# 10_Misc.net
KiCad netlist of a schematic drawn in Altium Designer
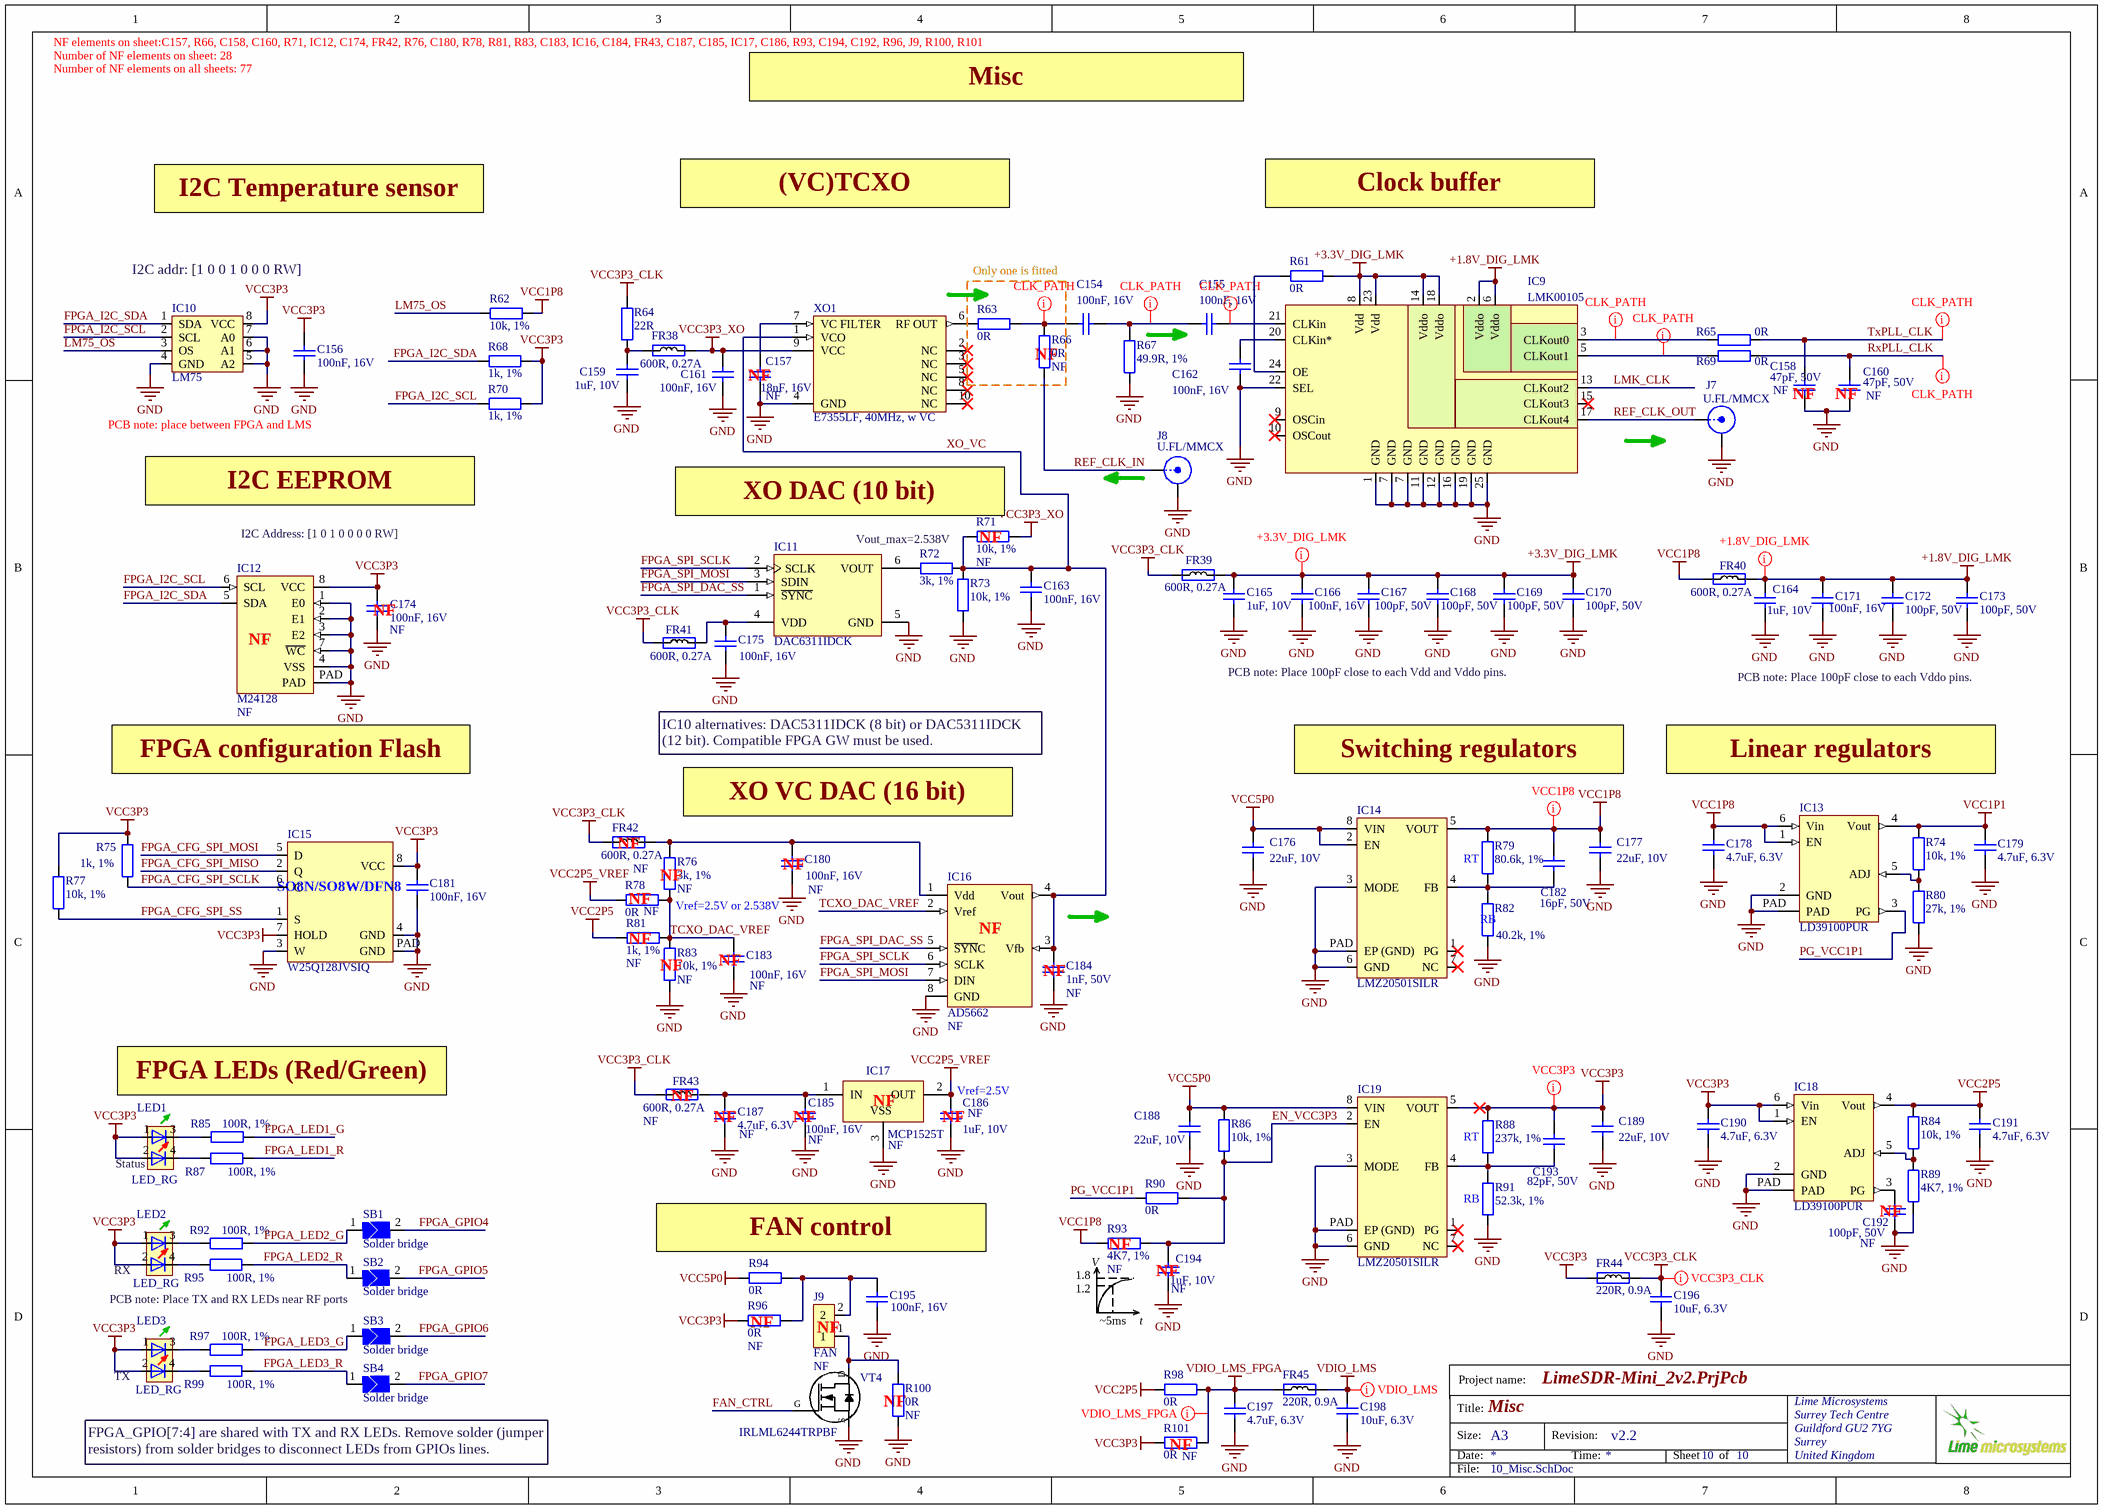
[diagram p0: 10_Misc.SchDoc]

(export (version "E")
  (design (tool "Eeschema 10.0.6"))
  (components
    (comp (ref "C154")
      (value "100nF, 16V")
      (footprint "CAP0402")
      (fields
        (field (name "MANUFACTURER") "Murata Electronics")
        (field (name "TOLERANCE") "10 %")
        (field (name "MANUFACTURER PART NUMBER") "GRM155R71C104KA88D")
      )
      (libsource (lib "LimeMicroAltiumLib_schLib") (part "Cap_0402"))
    )
    (comp (ref "C155")
      (value "100nF, 16V")
      (footprint "CAP0402")
      (fields
        (field (name "MANUFACTURER") "Murata Electronics")
        (field (name "TOLERANCE") "10 %")
        (field (name "MANUFACTURER PART NUMBER") "GRM155R71C104KA88D")
      )
      (libsource (lib "LimeMicroAltiumLib_schLib") (part "Cap_0402"))
    )
    (comp (ref "C156")
      (value "100nF, 16V")
      (footprint "CAP0402")
      (fields
        (field (name "TOLERANCE") "10 %")
        (field (name "MANUFACTURER") "Murata Electronics")
        (field (name "MANUFACTURER PART NUMBER") "GRM155R71C104KA88D")
      )
      (libsource (lib "LimeFPGAboard_schLib") (part "Cap_0603"))
    )
    (comp (ref "C157")
      (value "18nF, 16V")
      (footprint "CAP0402")
      (fields
        (field (name "ASSEMBLY INFO") "NF")
        (field (name "MANUFACTURER") "Yageo")
        (field (name "TOLERANCE") "±10%")
      )
      (libsource (lib "LimeMicroAltiumLib_schLib") (part "Cap_0402"))
    )
    (comp (ref "C158")
      (value "47pF, 50V")
      (footprint "CAP0402")
      (fields
        (field (name "TOLERANCE") "±1%")
        (field (name "MANUFACTURER") "TDK Corporation")
        (field (name "ASSEMBLY INFO") "NF")
      )
      (libsource (lib "LimeMicroAltiumLib_schLib") (part "Cap_0402"))
    )
    (comp (ref "C159")
      (value "1uF, 10V")
      (footprint "CAP0402")
      (fields (field (name "MANUFACTURER") "TDK"))
      (libsource (lib "LimeMicroAltiumLib_schLib") (part "Cap_0402"))
    )
    (comp (ref "C160")
      (value "47pF, 50V")
      (footprint "CAP0402")
      (fields
        (field (name "TOLERANCE") "±1%")
        (field (name "MANUFACTURER") "TDK Corporation")
        (field (name "ASSEMBLY INFO") "NF")
      )
      (libsource (lib "LimeMicroAltiumLib_schLib") (part "Cap_0402"))
    )
    (comp (ref "C161")
      (value "100nF, 16V")
      (footprint "CAP0402")
      (fields
        (field (name "MANUFACTURER") "Murata Electronics")
        (field (name "TOLERANCE") "10 %")
        (field (name "MANUFACTURER PART NUMBER") "GRM155R71C104KA88D")
      )
      (libsource (lib "LimeMicroAltiumLib_schLib") (part "Cap_0402"))
    )
    (comp (ref "C162")
      (value "100nF, 16V")
      (footprint "CAP0402")
      (fields
        (field (name "MANUFACTURER") "Murata Electronics")
        (field (name "TOLERANCE") "10 %")
        (field (name "MANUFACTURER PART NUMBER") "GRM155R71C104KA88D")
      )
      (libsource (lib "LimeMicroAltiumLib_schLib") (part "Cap_0402"))
    )
    (comp (ref "C163")
      (value "100nF, 16V")
      (footprint "CAP0402")
      (fields
        (field (name "MANUFACTURER") "Murata Electronics")
        (field (name "TOLERANCE") "10 %")
        (field (name "MANUFACTURER PART NUMBER") "GRM155R71C104KA88D")
      )
      (libsource (lib "LimeMicroAltiumLib_schLib") (part "Cap_0402"))
    )
    (comp (ref "C164")
      (value "1uF, 10V")
      (footprint "CAP0402")
      (fields (field (name "MANUFACTURER") "TDK"))
      (libsource (lib "LimeMicroAltiumLib_schLib") (part "Cap_0402"))
    )
    (comp (ref "C165")
      (value "1uF, 10V")
      (footprint "CAP0402")
      (fields (field (name "MANUFACTURER") "TDK"))
      (libsource (lib "LimeMicroAltiumLib_schLib") (part "Cap_0402"))
    )
    (comp (ref "C166")
      (value "100nF, 16V")
      (footprint "CAP0402")
      (fields
        (field (name "MANUFACTURER") "Murata Electronics")
        (field (name "TOLERANCE") "10 %")
        (field (name "MANUFACTURER PART NUMBER") "GRM155R71C104KA88D")
      )
      (libsource (lib "LimeMicroAltiumLib_schLib") (part "Cap_0402"))
    )
    (comp (ref "C167")
      (value "100pF, 50V")
      (footprint "CAP0402")
      (fields (field (name "MANUFACTURER") "Yageo") (field (name "TOLERANCE") "±5%"))
      (libsource (lib "LimeMicroAltiumLib_schLib") (part "Cap_0402"))
    )
    (comp (ref "C168")
      (value "100pF, 50V")
      (footprint "CAP0402")
      (fields (field (name "MANUFACTURER") "Yageo") (field (name "TOLERANCE") "±5%"))
      (libsource (lib "LimeMicroAltiumLib_schLib") (part "Cap_0402"))
    )
    (comp (ref "C169")
      (value "100pF, 50V")
      (footprint "CAP0402")
      (fields (field (name "MANUFACTURER") "Yageo") (field (name "TOLERANCE") "±5%"))
      (libsource (lib "LimeMicroAltiumLib_schLib") (part "Cap_0402"))
    )
    (comp (ref "C170")
      (value "100pF, 50V")
      (footprint "CAP0402")
      (fields (field (name "MANUFACTURER") "Yageo") (field (name "TOLERANCE") "±5%"))
      (libsource (lib "LimeMicroAltiumLib_schLib") (part "Cap_0402"))
    )
    (comp (ref "C171")
      (value "100nF, 16V")
      (footprint "CAP0402")
      (fields
        (field (name "MANUFACTURER") "Murata Electronics")
        (field (name "TOLERANCE") "10 %")
        (field (name "MANUFACTURER PART NUMBER") "GRM155R71C104KA88D")
      )
      (libsource (lib "LimeMicroAltiumLib_schLib") (part "Cap_0402"))
    )
    (comp (ref "C172")
      (value "100pF, 50V")
      (footprint "CAP0402")
      (fields (field (name "MANUFACTURER") "Yageo") (field (name "TOLERANCE") "±5%"))
      (libsource (lib "LimeMicroAltiumLib_schLib") (part "Cap_0402"))
    )
    (comp (ref "C173")
      (value "100pF, 50V")
      (footprint "CAP0402")
      (fields (field (name "MANUFACTURER") "Yageo") (field (name "TOLERANCE") "±5%"))
      (libsource (lib "LimeMicroAltiumLib_schLib") (part "Cap_0402"))
    )
    (comp (ref "C174")
      (value "100nF, 16V")
      (footprint "CAP0402")
      (fields
        (field (name "TOLERANCE") "10 %")
        (field (name "MANUFACTURER") "Murata Electronics")
        (field (name "MANUFACTURER PART NUMBER") "GRM155R71C104KA88D")
        (field (name "ASSEMBLY INFO") "NF")
      )
      (libsource (lib "LimeFPGAboard_schLib") (part "Cap_0603"))
    )
    (comp (ref "C175")
      (value "100nF, 16V")
      (footprint "CAP0402")
      (fields
        (field (name "TOLERANCE") "10 %")
        (field (name "MANUFACTURER") "Murata Electronics")
        (field (name "MANUFACTURER PART NUMBER") "GRM155R71C104KA88D")
      )
      (libsource (lib "LimeFPGAboard_schLib") (part "Cap_0603"))
    )
    (comp (ref "C176")
      (value "22uF, 10V")
      (footprint "CAP0603")
      (fields (field (name "TOLERANCE") "20 %") (field (name "MANUFACTURER") "TDK Corporation"))
      (libsource (lib "LimeFPGAboard_schLib") (part "Cap_0603"))
    )
    (comp (ref "C177")
      (value "22uF, 10V")
      (footprint "CAP0603")
      (fields (field (name "TOLERANCE") "20 %") (field (name "MANUFACTURER") "TDK Corporation"))
      (libsource (lib "LimeFPGAboard_schLib") (part "Cap_0603"))
    )
    (comp (ref "C178")
      (value "4.7uF, 6.3V")
      (footprint "CAP0402")
      (fields
        (field (name "MANUFACTURER") "Murata Electronics North America")
        (field (name "TOLERANCE") "±20%")
      )
      (libsource (lib "LimeMicroAltiumLib_schLib") (part "Cap_0402"))
    )
    (comp (ref "C179")
      (value "4.7uF, 6.3V")
      (footprint "CAP0402")
      (fields
        (field (name "MANUFACTURER") "Murata Electronics North America")
        (field (name "TOLERANCE") "±20%")
      )
      (libsource (lib "LimeMicroAltiumLib_schLib") (part "Cap_0402"))
    )
    (comp (ref "C180")
      (value "100nF, 16V")
      (footprint "CAP0402")
      (fields
        (field (name "TOLERANCE") "10 %")
        (field (name "MANUFACTURER") "Murata Electronics")
        (field (name "MANUFACTURER PART NUMBER") "GRM155R71C104KA88D")
        (field (name "ASSEMBLY INFO") "NF")
      )
      (libsource (lib "LimeFPGAboard_schLib") (part "Cap_0603"))
    )
    (comp (ref "C181")
      (value "100nF, 16V")
      (footprint "CAP0402")
      (fields
        (field (name "TOLERANCE") "10 %")
        (field (name "MANUFACTURER") "Murata Electronics")
        (field (name "MANUFACTURER PART NUMBER") "GRM155R71C104KA88D")
      )
      (libsource (lib "LimeFPGAboard_schLib") (part "Cap_0603"))
    )
    (comp (ref "C182")
      (value "16pF, 50V")
      (footprint "CAP0402")
      (fields (field (name "MANUFACTURER") "Yageo") (field (name "TOLERANCE") "5%"))
      (libsource (lib "LimeMicroAltiumLib_schLib") (part "Cap_0402"))
    )
    (comp (ref "C183")
      (value "100nF, 16V")
      (footprint "CAP0402")
      (fields
        (field (name "TOLERANCE") "10 %")
        (field (name "MANUFACTURER") "Murata Electronics")
        (field (name "ASSEMBLY INFO") "NF")
      )
      (libsource (lib "") (part "Cap_0603_1"))
    )
    (comp (ref "C184")
      (value "1nF, 50V")
      (footprint "CAP0402")
      (fields
        (field (name "ASSEMBLY INFO") "NF")
        (field (name "TOLERANCE") "10 %")
        (field (name "MANUFACTURER") "Murata Electronics")
      )
      (libsource (lib "") (part "Cap_0402_1"))
    )
    (comp (ref "C185")
      (value "100nF, 16V")
      (footprint "CAP0402")
      (fields
        (field (name "TOLERANCE") "10 %")
        (field (name "MANUFACTURER") "Murata Electronics")
        (field (name "ASSEMBLY INFO") "NF")
      )
      (libsource (lib "") (part "Cap_0603_1"))
    )
    (comp (ref "C186")
      (value "1uF, 10V")
      (footprint "CAP0402")
      (fields (field (name "ASSEMBLY INFO") "NF") (field (name "MANUFACTURER") "TDK"))
      (libsource (lib "LimeMicroAltiumLib_schLib") (part "Cap_0402"))
    )
    (comp (ref "C187")
      (value "4.7uF, 6.3V")
      (footprint "CAP0402")
      (fields
        (field (name "ASSEMBLY INFO") "NF")
        (field (name "MANUFACTURER") "Murata Electronics North America")
        (field (name "TOLERANCE") "±20%")
      )
      (libsource (lib "LimeMicroAltiumLib_schLib") (part "Cap_0402"))
    )
    (comp (ref "C188")
      (value "22uF, 10V")
      (footprint "CAP0603")
      (fields (field (name "TOLERANCE") "20 %") (field (name "MANUFACTURER") "TDK Corporation"))
      (libsource (lib "LimeFPGAboard_schLib") (part "Cap_0603"))
    )
    (comp (ref "C189")
      (value "22uF, 10V")
      (footprint "CAP0603")
      (fields (field (name "TOLERANCE") "20 %") (field (name "MANUFACTURER") "TDK Corporation"))
      (libsource (lib "LimeFPGAboard_schLib") (part "Cap_0603"))
    )
    (comp (ref "C190")
      (value "4.7uF, 6.3V")
      (footprint "CAP0402")
      (fields
        (field (name "MANUFACTURER") "Murata Electronics North America")
        (field (name "TOLERANCE") "±20%")
      )
      (libsource (lib "LimeMicroAltiumLib_schLib") (part "Cap_0402"))
    )
    (comp (ref "C191")
      (value "4.7uF, 6.3V")
      (footprint "CAP0402")
      (fields
        (field (name "MANUFACTURER") "Murata Electronics North America")
        (field (name "TOLERANCE") "±20%")
      )
      (libsource (lib "LimeMicroAltiumLib_schLib") (part "Cap_0402"))
    )
    (comp (ref "C192")
      (value "100pF, 50V")
      (footprint "CAP0402")
      (fields
        (field (name "ASSEMBLY INFO") "NF")
        (field (name "MANUFACTURER") "Yageo")
        (field (name "TOLERANCE") "±5%")
      )
      (libsource (lib "LimeMicroAltiumLib_schLib") (part "Cap_0402"))
    )
    (comp (ref "C193")
      (value "82pF, 50V")
      (footprint "CAP0402")
      (description "Cap Cer 82PF 50V Ch 0402")
      (fields (field (name "MANUFACTURER") "Taiyo Yuden"))
      (libsource (lib "LimeMicroAltiumLib_schLib") (part "Cap_0402"))
    )
    (comp (ref "C194")
      (value "1uF, 10V")
      (footprint "CAP0402")
      (fields (field (name "ASSEMBLY INFO") "NF") (field (name "MANUFACTURER") "TDK"))
      (libsource (lib "LimeMicroAltiumLib_schLib") (part "Cap_0402"))
    )
    (comp (ref "C195")
      (value "100nF, 16V")
      (footprint "CAP0402")
      (fields
        (field (name "TOLERANCE") "10 %")
        (field (name "MANUFACTURER") "Murata Electronics")
        (field (name "MANUFACTURER PART NUMBER") "GRM155R71C104KA88D")
      )
      (libsource (lib "LimeFPGAboard_schLib") (part "Cap_0603"))
    )
    (comp (ref "C196")
      (value "10uF, 6.3V")
      (footprint "CAP0603")
      (fields (field (name "TOLERANCE") "±20%") (field (name "MANUFACTURER") "Yageo"))
      (libsource (lib "LimeFPGAboard_schLib") (part "Cap_0603"))
    )
    (comp (ref "C197")
      (value "4.7uF, 6.3V")
      (footprint "CAP0402")
      (fields
        (field (name "MANUFACTURER") "Murata Electronics North America")
        (field (name "TOLERANCE") "±20%")
      )
      (libsource (lib "LimeMicroAltiumLib_schLib") (part "Cap_0402"))
    )
    (comp (ref "C198")
      (value "10uF, 6.3V")
      (footprint "CAP0603")
      (fields (field (name "TOLERANCE") "±20%") (field (name "MANUFACTURER") "Yageo"))
      (libsource (lib "LimeFPGAboard_schLib") (part "Cap_0603"))
    )
    (comp (ref "FR38")
      (value "600R, 0.27A")
      (footprint "RES0201")
      (fields (field (name "MANUFACTURER") "Taiyo Yuden"))
      (libsource (lib "LimeMicroAltiumLib_schLib") (part "Ferrite"))
    )
    (comp (ref "FR39")
      (value "600R, 0.27A")
      (footprint "RES0201")
      (fields (field (name "MANUFACTURER") "Taiyo Yuden"))
      (libsource (lib "LimeMicroAltiumLib_schLib") (part "Ferrite"))
    )
    (comp (ref "FR40")
      (value "600R, 0.27A")
      (footprint "RES0201")
      (fields (field (name "MANUFACTURER") "Taiyo Yuden"))
      (libsource (lib "LimeMicroAltiumLib_schLib") (part "Ferrite"))
    )
    (comp (ref "FR41")
      (value "600R, 0.27A")
      (footprint "RES0201")
      (fields (field (name "MANUFACTURER") "Taiyo Yuden"))
      (libsource (lib "LimeMicroAltiumLib_schLib") (part "Ferrite"))
    )
    (comp (ref "FR42")
      (value "600R, 0.27A")
      (footprint "RES0201")
      (fields (field (name "MANUFACTURER") "Taiyo Yuden") (field (name "ASSEMBLY INFO") "NF"))
      (libsource (lib "LimeMicroAltiumLib_schLib") (part "Ferrite"))
    )
    (comp (ref "FR43")
      (value "600R, 0.27A")
      (footprint "RES0201")
      (fields (field (name "MANUFACTURER") "Taiyo Yuden") (field (name "ASSEMBLY INFO") "NF"))
      (libsource (lib "LimeMicroAltiumLib_schLib") (part "Ferrite"))
    )
    (comp (ref "FR44")
      (value "220R, 0.9A")
      (footprint "RES0402")
      (fields (field (name "MANUFACTURER") "TDK Corporation"))
      (libsource (lib "LimeFPGAboard_schLib") (part "Ferrite"))
    )
    (comp (ref "FR45")
      (value "220R, 0.9A")
      (footprint "RES0402")
      (fields (field (name "MANUFACTURER") "TDK Corporation"))
      (libsource (lib "LimeFPGAboard_schLib") (part "Ferrite"))
    )
    (comp (ref "IC9")
      (value "LMK00105")
      (footprint "LMK00105SQ")
      (fields (field (name "MANUFACTURER") "Texas Instruments"))
      (libsource (lib "LimeMicroAltiumLib_schLib") (part "LMK00105"))
    )
    (comp (ref "IC10")
      (value "LM75")
      (footprint "HWSON8_LM75")
      (fields (field (name "MANUFACTURER") "NXP Semiconductors"))
      (libsource (lib "LimeMicroAltiumLib_schLib") (part "LM75"))
    )
    (comp (ref "IC11")
      (value "DAC6311IDCK")
      (footprint "AD5601_SOT23-6")
      (fields (field (name "MANUFACTURER") "Texas Instruments"))
      (libsource (lib "LimeMicroAltiumLib_schLib") (part "AD5601BKSZ-REEL7"))
    )
    (comp (ref "IC12")
      (value "M24128")
      (footprint "M24128-DFMC6TG")
      (fields (field (name "MANUFACTURER") "STMicroelectronics") (field (name "ASSEMBLY INFO") "NF"))
      (libsource (lib "LimeMicroAltiumLib_schLib") (part "M24128-DFMC6TG"))
    )
    (comp (ref "IC13")
      (value "LD39100PUR")
      (footprint "LD39100PUR")
      (fields (field (name "MANUFACTURER") "STMicroelectronics"))
      (libsource (lib "LimeMicroAltiumLib_schLib") (part "LD39100PUR"))
    )
    (comp (ref "IC14")
      (value "LMZ20501SILR")
      (footprint "LMZ20501SILR_DC-DC_8-SMD")
      (fields (field (name "MANUFACTURER") "Texas Instruments"))
      (libsource (lib "LimeMicroAltiumLib_schLib_r04") (part "LMZ20501SILR_DC-DC"))
    )
    (comp (ref "IC15")
      (value "W25Q128JVSIQ")
      (footprint "S25FL164K_WSON8_DFN6")
      (fields (field (name "MANUFACTURER") "Winbond"))
      (libsource (lib "LimeMicroAltiumLib_schLib_r03") (part "M25P40_with_pad"))
    )
    (comp (ref "IC16")
      (value "AD5662")
      (footprint "AD5662_SOT23-8")
      (fields (field (name "MANUFACTURER") "Analog Devices Inc.") (field (name "ASSEMBLY INFO") "NF"))
      (libsource (lib "LimeMicroAltiumLib_schLib") (part "AD5662"))
    )
    (comp (ref "IC17")
      (value "MCP1525T")
      (footprint "SOT23-3_v2")
      (description "2.5V Voltage Reference, 3-Pin SOT-23, Industrial Temperature, Tape and Reel")
      (fields
        (field (name "MANUFACTURER") "Microchip Technology")
        (field (name "TOLERANCE") "±1%")
        (field (name "ASSEMBLY INFO") "NF")
      )
      (libsource (lib "LimeMicroAltiumLib_schLib") (part "MCP1525T-I/TT"))
    )
    (comp (ref "IC18")
      (value "LD39100PUR")
      (footprint "LD39100PUR")
      (fields (field (name "MANUFACTURER") "STMicroelectronics"))
      (libsource (lib "LimeMicroAltiumLib_schLib") (part "LD39100PUR"))
    )
    (comp (ref "IC19")
      (value "LMZ20501SILR")
      (footprint "LMZ20501SILR_DC-DC_8-SMD")
      (fields (field (name "MANUFACTURER") "Texas Instruments"))
      (libsource (lib "LimeMicroAltiumLib_schLib_r04") (part "LMZ20501SILR_DC-DC"))
    )
    (comp (ref "J7")
      (value "U.FL/MMCX")
      (footprint "MMCX_UFL_conn_u")
      (description "CONN UMC RCPT STR 50 OHM SMD")
      (fields (field (name "MANUFACTURER") "Molex, LLC"))
      (libsource (lib "LimeMicroAltiumLib_schLib") (part "RF_IF_connector"))
    )
    (comp (ref "J8")
      (value "U.FL/MMCX")
      (footprint "MMCX_UFL_conn_u")
      (description "CONN UMC RCPT STR 50 OHM SMD")
      (fields (field (name "MANUFACTURER") "Molex, LLC"))
      (libsource (lib "LimeMicroAltiumLib_schLib") (part "RF_IF_connector"))
    )
    (comp (ref "J9")
      (value "FAN")
      (footprint "Header2x1_TH_v2")
      (fields (field (name "ASSEMBLY INFO") "NF") (field (name "MANUFACTURER") "3M"))
      (libsource (lib "LimeFPGAboard_schLib") (part "Jumper"))
    )
    (comp (ref "LED1")
      (value "LED_RG")
      (footprint "LED-2x0603")
      (fields (field (name "MANUFACTURER") "Avago Technologies US Inc."))
      (libsource (lib "LimeMicroAltiumLib_schLib") (part "LED_green_red_SMD"))
    )
    (comp (ref "LED2")
      (value "LED_RG")
      (footprint "LED-2x0603")
      (fields (field (name "MANUFACTURER") "Avago Technologies US Inc."))
      (libsource (lib "LimeMicroAltiumLib_schLib") (part "LED_green_red_SMD"))
    )
    (comp (ref "LED3")
      (value "LED_RG")
      (footprint "LED-2x0603")
      (fields (field (name "MANUFACTURER") "Avago Technologies US Inc."))
      (libsource (lib "LimeMicroAltiumLib_schLib") (part "LED_green_red_SMD"))
    )
    (comp (ref "R61")
      (value "0R")
      (footprint "RES0402")
      (fields (field (name "MANUFACTURER") "Yageo") (field (name "TOLERANCE") "Jumper"))
      (libsource (lib "LimeMicroAltiumLib_schLib") (part "Res_0402"))
    )
    (comp (ref "R62")
      (value "10k, 1%")
      (footprint "RES0402")
      (fields (field (name "MANUFACTURER") "Yageo") (field (name "TOLERANCE") "±1%"))
      (libsource (lib "LimeMicroAltiumLib_schLib") (part "Res_0402"))
    )
    (comp (ref "R63")
      (value "0R")
      (footprint "RES0402")
      (fields (field (name "MANUFACTURER") "Yageo") (field (name "TOLERANCE") "Jumper"))
      (libsource (lib "LimeMicroAltiumLib_schLib") (part "Res_0402"))
    )
    (comp (ref "R64")
      (value "22R")
      (footprint "RES0402")
      (fields (field (name "TOLERANCE") "±1%") (field (name "MANUFACTURER") "Yageo"))
      (libsource (lib "LimeFPGAboard_schLib") (part "Res_0402"))
    )
    (comp (ref "R65")
      (value "0R")
      (footprint "RES0402")
      (fields (field (name "MANUFACTURER") "Yageo") (field (name "TOLERANCE") "Jumper"))
      (libsource (lib "LimeFPGAboard_schLib") (part "Res_0402"))
    )
    (comp (ref "R66")
      (value "0R")
      (footprint "RES0402")
      (fields
        (field (name "ASSEMBLY INFO") "NF")
        (field (name "MANUFACTURER") "Yageo")
        (field (name "TOLERANCE") "Jumper")
      )
      (libsource (lib "LimeMicroAltiumLib_schLib") (part "Res_0402"))
    )
    (comp (ref "R67")
      (value "49.9R, 1%")
      (footprint "RES0402")
      (fields
        (field (name "TOLERANCE") "±1%")
        (field (name "MANUFACTURER") "Samsung Electro-Mechanics America, Inc.")
      )
      (libsource (lib "LimeMicroAltiumLib_schLib") (part "Res_0402"))
    )
    (comp (ref "R68")
      (value "1k, 1%")
      (footprint "RES0402")
      (fields (field (name "MANUFACTURER") "Stackpole Electronics Inc") (field (name "TOLERANCE") "±1%"))
      (libsource (lib "LimeMicroAltiumLib_schLib") (part "Res_0402"))
    )
    (comp (ref "R69")
      (value "0R")
      (footprint "RES0402")
      (fields (field (name "MANUFACTURER") "Yageo") (field (name "TOLERANCE") "Jumper"))
      (libsource (lib "LimeFPGAboard_schLib") (part "Res_0402"))
    )
    (comp (ref "R70")
      (value "1k, 1%")
      (footprint "RES0402")
      (fields (field (name "MANUFACTURER") "Stackpole Electronics Inc") (field (name "TOLERANCE") "±1%"))
      (libsource (lib "LimeMicroAltiumLib_schLib") (part "Res_0402"))
    )
    (comp (ref "R71")
      (value "10k, 1%")
      (footprint "RES0402")
      (fields
        (field (name "ASSEMBLY INFO") "NF")
        (field (name "MANUFACTURER") "Yageo")
        (field (name "TOLERANCE") "±1%")
      )
      (libsource (lib "LimeMicroAltiumLib_schLib") (part "Res_0402"))
    )
    (comp (ref "R72")
      (value "3k, 1%")
      (footprint "RES0402")
      (fields (field (name "TOLERANCE") "±1%") (field (name "MANUFACTURER") "Vishay Dale"))
      (libsource (lib "LimeMicroAltiumLib_schLib") (part "Res_0402"))
    )
    (comp (ref "R73")
      (value "10k, 1%")
      (footprint "RES0402")
      (fields (field (name "MANUFACTURER") "Yageo") (field (name "TOLERANCE") "±1%"))
      (libsource (lib "LimeMicroAltiumLib_schLib") (part "Res_0402"))
    )
    (comp (ref "R74")
      (value "10k, 1%")
      (footprint "RES0402")
      (fields (field (name "MANUFACTURER") "Yageo") (field (name "TOLERANCE") "±1%"))
      (libsource (lib "LimeMicroAltiumLib_schLib") (part "Res_0402"))
    )
    (comp (ref "R75")
      (value "1k, 1%")
      (footprint "RES0402")
      (fields (field (name "MANUFACTURER") "Stackpole Electronics Inc") (field (name "TOLERANCE") "±1%"))
      (libsource (lib "LimeMicroAltiumLib_schLib") (part "Res_0402"))
    )
    (comp (ref "R76")
      (value "3k, 1%")
      (footprint "RES0402")
      (fields
        (field (name "ASSEMBLY INFO") "NF")
        (field (name "TOLERANCE") "±1%")
        (field (name "MANUFACTURER") "Vishay Dale")
      )
      (libsource (lib "") (part "Res_0402_1"))
    )
    (comp (ref "R77")
      (value "10k, 1%")
      (footprint "RES0402")
      (fields (field (name "MANUFACTURER") "Yageo") (field (name "TOLERANCE") "±1%"))
      (libsource (lib "LimeMicroAltiumLib_schLib") (part "Res_0402"))
    )
    (comp (ref "R78")
      (value "0R")
      (footprint "RES0402")
      (fields
        (field (name "ASSEMBLY INFO") "NF")
        (field (name "MANUFACTURER") "Yageo")
        (field (name "TOLERANCE") "Jumper")
      )
      (libsource (lib "LimeMicroAltiumLib_schLib") (part "Res_0402"))
    )
    (comp (ref "R79")
      (value "80.6k, 1%")
      (footprint "RES0402")
      (fields (field (name "MANUFACTURER") "Stackpole Electronics") (field (name "TOLERANCE") "1%"))
      (libsource (lib "LimeMicroAltiumLib_schLib") (part "Res_0402"))
    )
    (comp (ref "R80")
      (value "27k, 1%")
      (footprint "RES0402")
      (fields (field (name "MANUFACTURER") "Yageo") (field (name "TOLERANCE") "1%"))
      (libsource (lib "LimeFPGAboard_schLib") (part "Res_0402"))
    )
    (comp (ref "R81")
      (value "1k, 1%")
      (footprint "RES0402")
      (fields
        (field (name "ASSEMBLY INFO") "NF")
        (field (name "MANUFACTURER") "Stackpole Electronics Inc")
        (field (name "TOLERANCE") "±1%")
      )
      (libsource (lib "") (part "Res_0402_1"))
    )
    (comp (ref "R82")
      (value "40.2k, 1%")
      (footprint "RES0402")
      (fields (field (name "MANUFACTURER") "Yageo") (field (name "TOLERANCE") "1%"))
      (libsource (lib "LimeMicroAltiumLib_schLib") (part "Res_0402"))
    )
    (comp (ref "R83")
      (value "10k, 1%")
      (footprint "RES0402")
      (fields
        (field (name "ASSEMBLY INFO") "NF")
        (field (name "MANUFACTURER") "Yageo")
        (field (name "TOLERANCE") "±1%")
      )
      (libsource (lib "") (part "Res_0402_1"))
    )
    (comp (ref "R84")
      (value "10k, 1%")
      (footprint "RES0402")
      (fields (field (name "MANUFACTURER") "Yageo") (field (name "TOLERANCE") "±1%"))
      (libsource (lib "LimeMicroAltiumLib_schLib") (part "Res_0402"))
    )
    (comp (ref "R85")
      (value "100R, 1%")
      (footprint "RES0402")
      (fields (field (name "TOLERANCE") "±1%") (field (name "MANUFACTURER") "Stackpole Electronics Inc."))
      (libsource (lib "LimeMicroAltiumLib_schLib") (part "Res_0402"))
    )
    (comp (ref "R86")
      (value "10k, 1%")
      (footprint "RES0402")
      (fields (field (name "MANUFACTURER") "Yageo") (field (name "TOLERANCE") "±1%"))
      (libsource (lib "LimeMicroAltiumLib_schLib") (part "Res_0402"))
    )
    (comp (ref "R87")
      (value "100R, 1%")
      (footprint "RES0402")
      (fields (field (name "TOLERANCE") "±1%") (field (name "MANUFACTURER") "Stackpole Electronics Inc."))
      (libsource (lib "LimeMicroAltiumLib_schLib") (part "Res_0402"))
    )
    (comp (ref "R88")
      (value "237k, 1%")
      (footprint "RES0402")
      (fields (field (name "MANUFACTURER") "Yageo") (field (name "TOLERANCE") "1%"))
      (libsource (lib "LimeMicroAltiumLib_schLib") (part "Res_0402"))
    )
    (comp (ref "R89")
      (value "4K7, 1%")
      (footprint "RES0402")
      (fields (field (name "MANUFACTURER") "Yageo") (field (name "TOLERANCE") "±1%"))
      (libsource (lib "LimeFPGAboard_schLib") (part "Res_0402"))
    )
    (comp (ref "R90")
      (value "0R")
      (footprint "RES0402")
      (fields (field (name "MANUFACTURER") "Yageo") (field (name "TOLERANCE") "Jumper"))
      (libsource (lib "LimeMicroAltiumLib_schLib") (part "Res_0402"))
    )
    (comp (ref "R91")
      (value "52.3k, 1%")
      (footprint "RES0402")
      (fields (field (name "MANUFACTURER") "Panasonic") (field (name "TOLERANCE") "1%"))
      (libsource (lib "LimeMicroAltiumLib_schLib") (part "Res_0402"))
    )
    (comp (ref "R92")
      (value "100R, 1%")
      (footprint "RES0402")
      (fields (field (name "TOLERANCE") "±1%") (field (name "MANUFACTURER") "Stackpole Electronics Inc."))
      (libsource (lib "LimeMicroAltiumLib_schLib") (part "Res_0402"))
    )
    (comp (ref "R93")
      (value "4K7, 1%")
      (footprint "RES0402")
      (fields
        (field (name "MANUFACTURER") "Yageo")
        (field (name "TOLERANCE") "±1%")
        (field (name "ASSEMBLY INFO") "NF")
      )
      (libsource (lib "LimeFPGAboard_schLib") (part "Res_0402"))
    )
    (comp (ref "R94")
      (value "0R")
      (footprint "RES0402")
      (fields (field (name "MANUFACTURER") "Yageo") (field (name "TOLERANCE") "Jumper"))
      (libsource (lib "LimeMicroAltiumLib_schLib") (part "Res_0402"))
    )
    (comp (ref "R95")
      (value "100R, 1%")
      (footprint "RES0402")
      (fields (field (name "TOLERANCE") "±1%") (field (name "MANUFACTURER") "Stackpole Electronics Inc."))
      (libsource (lib "LimeMicroAltiumLib_schLib") (part "Res_0402"))
    )
    (comp (ref "R96")
      (value "0R")
      (footprint "RES0402")
      (fields
        (field (name "ASSEMBLY INFO") "NF")
        (field (name "MANUFACTURER") "Yageo")
        (field (name "TOLERANCE") "Jumper")
      )
      (libsource (lib "LimeMicroAltiumLib_schLib") (part "Res_0402"))
    )
    (comp (ref "R97")
      (value "100R, 1%")
      (footprint "RES0402")
      (fields (field (name "TOLERANCE") "±1%") (field (name "MANUFACTURER") "Stackpole Electronics Inc."))
      (libsource (lib "LimeMicroAltiumLib_schLib") (part "Res_0402"))
    )
    (comp (ref "R98")
      (value "0R")
      (footprint "RES0402")
      (fields (field (name "MANUFACTURER") "Yageo") (field (name "TOLERANCE") "Jumper"))
      (libsource (lib "LimeFPGAboard_schLib") (part "Res_0402"))
    )
    (comp (ref "R99")
      (value "100R, 1%")
      (footprint "RES0402")
      (fields (field (name "TOLERANCE") "±1%") (field (name "MANUFACTURER") "Stackpole Electronics Inc."))
      (libsource (lib "LimeMicroAltiumLib_schLib") (part "Res_0402"))
    )
    (comp (ref "R100")
      (value "0R")
      (footprint "RES0402")
      (fields
        (field (name "ASSEMBLY INFO") "NF")
        (field (name "MANUFACTURER") "Yageo")
        (field (name "TOLERANCE") "Jumper")
      )
      (libsource (lib "LimeMicroAltiumLib_schLib") (part "Res_0402"))
    )
    (comp (ref "R101")
      (value "0R")
      (footprint "RES0402")
      (fields
        (field (name "MANUFACTURER") "Yageo")
        (field (name "ASSEMBLY INFO") "NF")
        (field (name "TOLERANCE") "Jumper")
      )
      (libsource (lib "LimeFPGAboard_schLib") (part "Res_0402"))
    )
    (comp (ref "SB1")
      (value "Solder bridge")
      (footprint "SOLDER_BRIDGE_TRIANGULAR_v2")
      (description "Can be shorted out using solder paste or 0402-1206 resistor")
      (fields (field (name "MANUFACTURER") "Yageo") (field (name "TOLERANCE") "Jumper"))
      (libsource (lib "LimeMicroAltiumLib_schLib_r03") (part "SOLDER_BRIDGE_TRIANGULAR"))
    )
    (comp (ref "SB2")
      (value "Solder bridge")
      (footprint "SOLDER_BRIDGE_TRIANGULAR_v2")
      (description "Can be shorted out using solder paste or 0402-1206 resistor")
      (fields (field (name "MANUFACTURER") "Yageo") (field (name "TOLERANCE") "Jumper"))
      (libsource (lib "LimeMicroAltiumLib_schLib_r03") (part "SOLDER_BRIDGE_TRIANGULAR"))
    )
    (comp (ref "SB3")
      (value "Solder bridge")
      (footprint "SOLDER_BRIDGE_TRIANGULAR_v2")
      (description "Can be shorted out using solder paste or 0402-1206 resistor")
      (fields (field (name "MANUFACTURER") "Yageo") (field (name "TOLERANCE") "Jumper"))
      (libsource (lib "LimeMicroAltiumLib_schLib_r03") (part "SOLDER_BRIDGE_TRIANGULAR"))
    )
    (comp (ref "SB4")
      (value "Solder bridge")
      (footprint "SOLDER_BRIDGE_TRIANGULAR_v2")
      (description "Can be shorted out using solder paste or 0402-1206 resistor")
      (fields (field (name "MANUFACTURER") "Yageo") (field (name "TOLERANCE") "Jumper"))
      (libsource (lib "LimeMicroAltiumLib_schLib_r03") (part "SOLDER_BRIDGE_TRIANGULAR"))
    )
    (comp (ref "VT4")
      (value "IRLML6244TRPBF")
      (footprint "SOT23-3")
      (description "NDS331N")
      (fields (field (name "MANUFACTURER") "Infineon Technologies"))
      (libsource (lib "LimeFPGAboard_schLib") (part "NDS331N"))
    )
    (comp (ref "XO1")
      (value "E7355LF, 40MHz, w VC")
      (footprint "RAKON_RTX5032A")
      (fields (field (name "MANUFACTURER") "Rakon"))
      (libsource (lib "LimeMicroAltiumLib_schLib") (part "Rakon_RTX5032A"))
    )
  )
  (nets
    (net (code "1") (name "+1.8V_DIG_LMK") (class "Default")
      (node (ref "C164") (pin "2") (pinfunction "2_2") (pintype "passive"))
      (node (ref "C171") (pin "2") (pinfunction "2_2") (pintype "passive"))
      (node (ref "C172") (pin "2") (pinfunction "2_2") (pintype "passive"))
      (node (ref "C173") (pin "2") (pinfunction "2_2") (pintype "passive"))
      (node (ref "FR40") (pin "2") (pinfunction "2_2") (pintype "passive"))
      (node (ref "IC9") (pin "2") (pinfunction "Vddo_2") (pintype "passive"))
      (node (ref "IC9") (pin "6") (pinfunction "Vddo_6") (pintype "passive"))
    )
    (net (code "2") (name "+3.3V_DIG_LMK") (class "Default")
      (node (ref "C165") (pin "2") (pinfunction "2_2") (pintype "passive"))
      (node (ref "C166") (pin "2") (pinfunction "2_2") (pintype "passive"))
      (node (ref "C167") (pin "2") (pinfunction "2_2") (pintype "passive"))
      (node (ref "C168") (pin "2") (pinfunction "2_2") (pintype "passive"))
      (node (ref "C169") (pin "2") (pinfunction "2_2") (pintype "passive"))
      (node (ref "C170") (pin "2") (pinfunction "2_2") (pintype "passive"))
      (node (ref "FR39") (pin "2") (pinfunction "2_2") (pintype "passive"))
      (node (ref "IC9") (pin "14") (pinfunction "Vddo_14") (pintype "passive"))
      (node (ref "IC9") (pin "18") (pinfunction "Vddo_18") (pintype "passive"))
      (node (ref "IC9") (pin "23") (pinfunction "Vdd_23") (pintype "passive"))
      (node (ref "IC9") (pin "8") (pinfunction "Vdd_8") (pintype "passive"))
      (node (ref "R61") (pin "2") (pinfunction "2_2") (pintype "passive"))
    )
    (net (code "3") (name "/EN_VCC3P3") (class "Default")
      (node (ref "C194") (pin "2") (pinfunction "2_2") (pintype "passive"))
      (node (ref "IC19") (pin "2") (pinfunction "EN_2") (pintype "input"))
      (node (ref "R86") (pin "1") (pinfunction "1_1") (pintype "passive"))
      (node (ref "R90") (pin "2") (pinfunction "2_2") (pintype "passive"))
      (node (ref "R93") (pin "1") (pinfunction "1_1") (pintype "passive"))
    )
    (net (code "4") (name "/FAN_CTRL") (class "Default")
      (node (ref "VT4") (pin "G") (pinfunction "G_G") (pintype "passive"))
    )
    (net (code "5") (name "/FPGA_CFG_SPI_MISO") (class "Default")
      (node (ref "IC15") (pin "2") (pinfunction "Q_2") (pintype "passive"))
    )
    (net (code "6") (name "/FPGA_CFG_SPI_MOSI") (class "Default")
      (node (ref "IC15") (pin "5") (pinfunction "D_5") (pintype "passive"))
    )
    (net (code "7") (name "/FPGA_CFG_SPI_SCLK") (class "Default")
      (node (ref "IC15") (pin "6") (pinfunction "C_6") (pintype "passive"))
      (node (ref "R75") (pin "1") (pinfunction "1_1") (pintype "passive"))
    )
    (net (code "8") (name "/FPGA_CFG_SPI_SS") (class "Default")
      (node (ref "IC15") (pin "1") (pinfunction "S_1") (pintype "passive"))
      (node (ref "R77") (pin "1") (pinfunction "1_1") (pintype "passive"))
    )
    (net (code "9") (name "/FPGA_GPIO4") (class "Default")
      (node (ref "SB1") (pin "2") (pinfunction "2_2") (pintype "passive"))
    )
    (net (code "10") (name "/FPGA_GPIO5") (class "Default")
      (node (ref "SB2") (pin "2") (pinfunction "2_2") (pintype "passive"))
    )
    (net (code "11") (name "/FPGA_GPIO6") (class "Default")
      (node (ref "SB3") (pin "2") (pinfunction "2_2") (pintype "passive"))
    )
    (net (code "12") (name "/FPGA_GPIO7") (class "Default")
      (node (ref "SB4") (pin "2") (pinfunction "2_2") (pintype "passive"))
    )
    (net (code "13") (name "/FPGA_I2C_SCL") (class "Default")
      (node (ref "IC10") (pin "2") (pinfunction "SCL_2") (pintype "passive"))
      (node (ref "IC12") (pin "6") (pinfunction "SCL_6") (pintype "input"))
      (node (ref "R70") (pin "2") (pinfunction "2_2") (pintype "passive"))
    )
    (net (code "14") (name "/FPGA_I2C_SDA") (class "Default")
      (node (ref "IC10") (pin "1") (pinfunction "SDA_1") (pintype "passive"))
      (node (ref "IC12") (pin "5") (pinfunction "SDA_5") (pintype "bidirectional"))
      (node (ref "R68") (pin "2") (pinfunction "2_2") (pintype "passive"))
    )
    (net (code "15") (name "/FPGA_LED1_G") (class "Default")
      (node (ref "R85") (pin "2") (pinfunction "2_2") (pintype "passive"))
    )
    (net (code "16") (name "/FPGA_LED1_R") (class "Default")
      (node (ref "R87") (pin "2") (pinfunction "2_2") (pintype "passive"))
    )
    (net (code "17") (name "/FPGA_LED2_G") (class "Default")
      (node (ref "R92") (pin "2") (pinfunction "2_2") (pintype "passive"))
      (node (ref "SB1") (pin "1") (pinfunction "1_1") (pintype "passive"))
    )
    (net (code "18") (name "/FPGA_LED2_R") (class "Default")
      (node (ref "R95") (pin "2") (pinfunction "2_2") (pintype "passive"))
      (node (ref "SB2") (pin "1") (pinfunction "1_1") (pintype "passive"))
    )
    (net (code "19") (name "/FPGA_LED3_G") (class "Default")
      (node (ref "R97") (pin "2") (pinfunction "2_2") (pintype "passive"))
      (node (ref "SB3") (pin "1") (pinfunction "1_1") (pintype "passive"))
    )
    (net (code "20") (name "/FPGA_LED3_R") (class "Default")
      (node (ref "R99") (pin "2") (pinfunction "2_2") (pintype "passive"))
      (node (ref "SB4") (pin "1") (pinfunction "1_1") (pintype "passive"))
    )
    (net (code "21") (name "/FPGA_SPI_DAC_SS") (class "Default")
      (node (ref "IC11") (pin "1") (pinfunction "~{SYNC}_1") (pintype "input"))
      (node (ref "IC16") (pin "5") (pinfunction "~{SYN}C_5") (pintype "input"))
    )
    (net (code "22") (name "/FPGA_SPI_MOSI") (class "Default")
      (node (ref "IC11") (pin "3") (pinfunction "SDIN_3") (pintype "input"))
      (node (ref "IC16") (pin "7") (pinfunction "DIN_7") (pintype "input"))
    )
    (net (code "23") (name "/FPGA_SPI_SCLK") (class "Default")
      (node (ref "IC11") (pin "2") (pinfunction "SCLK_2") (pintype "input"))
      (node (ref "IC16") (pin "6") (pinfunction "SCLK_6") (pintype "input"))
    )
    (net (code "24") (name "/LM75_OS") (class "Default")
      (node (ref "IC10") (pin "3") (pinfunction "OS_3") (pintype "passive"))
      (node (ref "R62") (pin "1") (pinfunction "1_1") (pintype "passive"))
    )
    (net (code "25") (name "/LMK_CLK") (class "Default")
      (node (ref "IC9") (pin "13") (pinfunction "CLKout2_13") (pintype "passive"))
    )
    (net (code "26") (name "/PG_VCC1P1") (class "Default")
      (node (ref "IC13") (pin "3") (pinfunction "PG_3") (pintype "output"))
      (node (ref "R90") (pin "1") (pinfunction "1_1") (pintype "passive"))
    )
    (net (code "27") (name "/REF_CLK_IN") (class "Default")
      (node (ref "J8") (pin "1") (pinfunction "X_1") (pintype "passive"))
      (node (ref "R66") (pin "1") (pinfunction "1_1") (pintype "passive"))
    )
    (net (code "28") (name "/REF_CLK_OUT") (class "Default")
      (node (ref "IC9") (pin "17") (pinfunction "CLKout4_17") (pintype "passive"))
      (node (ref "J7") (pin "1") (pinfunction "X_1") (pintype "passive"))
    )
    (net (code "29") (name "/RxPLL_CLK") (class "Default")
      (node (ref "C160") (pin "2") (pinfunction "2_2") (pintype "passive"))
      (node (ref "R69") (pin "1") (pinfunction "1_1") (pintype "passive"))
    )
    (net (code "30") (name "/TCXO_DAC_VREF") (class "Default")
      (node (ref "C183") (pin "1") (pinfunction "1_1") (pintype "passive"))
      (node (ref "IC16") (pin "2") (pinfunction "Vref_2") (pintype "input"))
      (node (ref "R76") (pin "1") (pinfunction "1_1") (pintype "passive"))
      (node (ref "R78") (pin "2") (pinfunction "2_2") (pintype "passive"))
      (node (ref "R81") (pin "1") (pinfunction "1_1") (pintype "passive"))
      (node (ref "R83") (pin "1") (pinfunction "1_1") (pintype "passive"))
    )
    (net (code "31") (name "/TxPLL_CLK") (class "Default")
      (node (ref "C158") (pin "2") (pinfunction "2_2") (pintype "passive"))
      (node (ref "R65") (pin "1") (pinfunction "1_1") (pintype "passive"))
    )
    (net (code "32") (name "/XO_VC") (class "Default")
      (node (ref "C163") (pin "2") (pinfunction "2_2") (pintype "passive"))
      (node (ref "C184") (pin "1") (pinfunction "1_1") (pintype "passive"))
      (node (ref "IC16") (pin "3") (pinfunction "Vfb_3") (pintype "input"))
      (node (ref "IC16") (pin "4") (pinfunction "Vout_4") (pintype "output"))
      (node (ref "R71") (pin "1") (pinfunction "1_1") (pintype "passive"))
      (node (ref "R72") (pin "1") (pinfunction "1_1") (pintype "passive"))
      (node (ref "R73") (pin "1") (pinfunction "1_1") (pintype "passive"))
      (node (ref "XO1") (pin "1") (pinfunction "VCO_1") (pintype "input"))
    )
    (net (code "33") (name "GND") (class "Default")
      (node (ref "C156") (pin "2") (pinfunction "2_2") (pintype "passive"))
      (node (ref "C157") (pin "1") (pinfunction "1_1") (pintype "passive"))
      (node (ref "C158") (pin "1") (pinfunction "1_1") (pintype "passive"))
      (node (ref "C159") (pin "1") (pinfunction "1_1") (pintype "passive"))
      (node (ref "C160") (pin "1") (pinfunction "1_1") (pintype "passive"))
      (node (ref "C161") (pin "1") (pinfunction "1_1") (pintype "passive"))
      (node (ref "C162") (pin "1") (pinfunction "1_1") (pintype "passive"))
      (node (ref "C163") (pin "1") (pinfunction "1_1") (pintype "passive"))
      (node (ref "C164") (pin "1") (pinfunction "1_1") (pintype "passive"))
      (node (ref "C165") (pin "1") (pinfunction "1_1") (pintype "passive"))
      (node (ref "C166") (pin "1") (pinfunction "1_1") (pintype "passive"))
      (node (ref "C167") (pin "1") (pinfunction "1_1") (pintype "passive"))
      (node (ref "C168") (pin "1") (pinfunction "1_1") (pintype "passive"))
      (node (ref "C169") (pin "1") (pinfunction "1_1") (pintype "passive"))
      (node (ref "C170") (pin "1") (pinfunction "1_1") (pintype "passive"))
      (node (ref "C171") (pin "1") (pinfunction "1_1") (pintype "passive"))
      (node (ref "C172") (pin "1") (pinfunction "1_1") (pintype "passive"))
      (node (ref "C173") (pin "1") (pinfunction "1_1") (pintype "passive"))
      (node (ref "C174") (pin "2") (pinfunction "2_2") (pintype "passive"))
      (node (ref "C175") (pin "2") (pinfunction "2_2") (pintype "passive"))
      (node (ref "C176") (pin "1") (pinfunction "1_1") (pintype "passive"))
      (node (ref "C177") (pin "1") (pinfunction "1_1") (pintype "passive"))
      (node (ref "C178") (pin "1") (pinfunction "1_1") (pintype "passive"))
      (node (ref "C179") (pin "1") (pinfunction "1_1") (pintype "passive"))
      (node (ref "C180") (pin "2") (pinfunction "2_2") (pintype "passive"))
      (node (ref "C181") (pin "2") (pinfunction "2_2") (pintype "passive"))
      (node (ref "C183") (pin "2") (pinfunction "2_2") (pintype "passive"))
      (node (ref "C184") (pin "2") (pinfunction "2_2") (pintype "passive"))
      (node (ref "C185") (pin "2") (pinfunction "2_2") (pintype "passive"))
      (node (ref "C186") (pin "1") (pinfunction "1_1") (pintype "passive"))
      (node (ref "C187") (pin "1") (pinfunction "1_1") (pintype "passive"))
      (node (ref "C188") (pin "1") (pinfunction "1_1") (pintype "passive"))
      (node (ref "C189") (pin "1") (pinfunction "1_1") (pintype "passive"))
      (node (ref "C190") (pin "1") (pinfunction "1_1") (pintype "passive"))
      (node (ref "C191") (pin "1") (pinfunction "1_1") (pintype "passive"))
      (node (ref "C192") (pin "1") (pinfunction "1_1") (pintype "passive"))
      (node (ref "C194") (pin "1") (pinfunction "1_1") (pintype "passive"))
      (node (ref "C195") (pin "2") (pinfunction "2_2") (pintype "passive"))
      (node (ref "C196") (pin "1") (pinfunction "1_1") (pintype "passive"))
      (node (ref "C197") (pin "1") (pinfunction "1_1") (pintype "passive"))
      (node (ref "C198") (pin "1") (pinfunction "1_1") (pintype "passive"))
      (node (ref "IC10") (pin "4") (pinfunction "GND_4") (pintype "passive"))
      (node (ref "IC10") (pin "5") (pinfunction "A2_5") (pintype "passive"))
      (node (ref "IC10") (pin "6") (pinfunction "A1_6") (pintype "passive"))
      (node (ref "IC10") (pin "7") (pinfunction "A0_7") (pintype "passive"))
      (node (ref "IC11") (pin "5") (pinfunction "GND_5") (pintype "power_in"))
      (node (ref "IC12") (pin "1") (pinfunction "E0_1") (pintype "input"))
      (node (ref "IC12") (pin "2") (pinfunction "E1_2") (pintype "input"))
      (node (ref "IC12") (pin "3") (pinfunction "E2_3") (pintype "input"))
      (node (ref "IC12") (pin "4") (pinfunction "VSS_4") (pintype "power_in"))
      (node (ref "IC12") (pin "7") (pinfunction "~{WC}_7") (pintype "input"))
      (node (ref "IC12") (pin "PAD") (pinfunction "PAD_PAD") (pintype "power_in"))
      (node (ref "IC13") (pin "2") (pinfunction "GND_2") (pintype "passive"))
      (node (ref "IC13") (pin "PAD") (pinfunction "PAD_PAD") (pintype "passive"))
      (node (ref "IC14") (pin "3") (pinfunction "MODE_3") (pintype "input"))
      (node (ref "IC14") (pin "6") (pinfunction "GND_6") (pintype "power_in"))
      (node (ref "IC14") (pin "PAD") (pinfunction "EP_(GND)_PAD") (pintype "passive"))
      (node (ref "IC15") (pin "3") (pinfunction "W_3") (pintype "passive"))
      (node (ref "IC15") (pin "4") (pinfunction "GND_4") (pintype "passive"))
      (node (ref "IC15") (pin "PAD") (pinfunction "GND_PAD") (pintype "passive"))
      (node (ref "IC16") (pin "8") (pinfunction "GND_8") (pintype "passive"))
      (node (ref "IC17") (pin "3") (pinfunction "VSS_3") (pintype "power_in"))
      (node (ref "IC18") (pin "2") (pinfunction "GND_2") (pintype "passive"))
      (node (ref "IC18") (pin "PAD") (pinfunction "PAD_PAD") (pintype "passive"))
      (node (ref "IC19") (pin "3") (pinfunction "MODE_3") (pintype "input"))
      (node (ref "IC19") (pin "6") (pinfunction "GND_6") (pintype "power_in"))
      (node (ref "IC19") (pin "PAD") (pinfunction "EP_(GND)_PAD") (pintype "passive"))
      (node (ref "IC9") (pin "1") (pinfunction "GND_1") (pintype "passive"))
      (node (ref "IC9") (pin "11") (pinfunction "GND_11") (pintype "passive"))
      (node (ref "IC9") (pin "12") (pinfunction "GND_12") (pintype "passive"))
      (node (ref "IC9") (pin "16") (pinfunction "GND_16") (pintype "passive"))
      (node (ref "IC9") (pin "19") (pinfunction "GND_19") (pintype "passive"))
      (node (ref "IC9") (pin "22") (pinfunction "SEL_22") (pintype "passive"))
      (node (ref "IC9") (pin "25") (pinfunction "GND_25") (pintype "passive"))
      (node (ref "IC9") (pin "7") (pinfunction "GND_7") (pintype "passive"))
      (node (ref "J7") (pin "2") (pinfunction "Y_2") (pintype "passive"))
      (node (ref "J8") (pin "2") (pinfunction "Y_2") (pintype "passive"))
      (node (ref "R100") (pin "1") (pinfunction "1_1") (pintype "passive"))
      (node (ref "R67") (pin "1") (pinfunction "1_1") (pintype "passive"))
      (node (ref "R73") (pin "2") (pinfunction "2_2") (pintype "passive"))
      (node (ref "R80") (pin "2") (pinfunction "2_2") (pintype "passive"))
      (node (ref "R82") (pin "1") (pinfunction "1_1") (pintype "passive"))
      (node (ref "R83") (pin "2") (pinfunction "2_2") (pintype "passive"))
      (node (ref "R89") (pin "2") (pinfunction "2_2") (pintype "passive"))
      (node (ref "R91") (pin "1") (pinfunction "1_1") (pintype "passive"))
      (node (ref "VT4") (pin "S") (pinfunction "S_S") (pintype "passive"))
      (node (ref "XO1") (pin "4") (pinfunction "GND_4") (pintype "passive"))
    )
    (net (code "34") (name "Net-(C154-Pad1)") (class "Default")
      (node (ref "C154") (pin "1") (pinfunction "1_1") (pintype "passive"))
      (node (ref "C155") (pin "2") (pinfunction "2_2") (pintype "passive"))
      (node (ref "R67") (pin "2") (pinfunction "2_2") (pintype "passive"))
    )
    (net (code "35") (name "Net-(C154-Pad2)") (class "Default")
      (node (ref "C154") (pin "2") (pinfunction "2_2") (pintype "passive"))
      (node (ref "R63") (pin "2") (pinfunction "2_2") (pintype "passive"))
      (node (ref "R66") (pin "2") (pinfunction "2_2") (pintype "passive"))
    )
    (net (code "36") (name "Net-(C159-Pad2)") (class "Default")
      (node (ref "C159") (pin "2") (pinfunction "2_2") (pintype "passive"))
      (node (ref "FR38") (pin "1") (pinfunction "1_1") (pintype "passive"))
      (node (ref "R64") (pin "1") (pinfunction "1_1") (pintype "passive"))
    )
    (net (code "37") (name "Net-(C195-Pad1)") (class "Default")
      (node (ref "C195") (pin "1") (pinfunction "1_1") (pintype "passive"))
      (node (ref "J9") (pin "2") (pinfunction "2_2") (pintype "passive"))
      (node (ref "R94") (pin "2") (pinfunction "2_2") (pintype "passive"))
      (node (ref "R96") (pin "2") (pinfunction "2_2") (pintype "passive"))
    )
    (net (code "38") (name "Net-(IC9-CLKin)") (class "Default")
      (node (ref "C155") (pin "1") (pinfunction "1_1") (pintype "passive"))
      (node (ref "IC9") (pin "21") (pinfunction "CLKin_21") (pintype "passive"))
    )
    (net (code "39") (name "Net-(IC9-CLKin*)") (class "Default")
      (node (ref "C162") (pin "2") (pinfunction "2_2") (pintype "passive"))
      (node (ref "IC9") (pin "20") (pinfunction "CLKin*_20") (pintype "passive"))
    )
    (net (code "40") (name "Net-(IC9-CLKout0)") (class "Default")
      (node (ref "IC9") (pin "3") (pinfunction "CLKout0_3") (pintype "passive"))
      (node (ref "R65") (pin "2") (pinfunction "2_2") (pintype "passive"))
    )
    (net (code "41") (name "Net-(IC9-CLKout1)") (class "Default")
      (node (ref "IC9") (pin "5") (pinfunction "CLKout1_5") (pintype "passive"))
      (node (ref "R69") (pin "2") (pinfunction "2_2") (pintype "passive"))
    )
    (net (code "42") (name "Net-(IC9-OE)") (class "Default")
      (node (ref "IC9") (pin "24") (pinfunction "OE_24") (pintype "passive"))
      (node (ref "R61") (pin "1") (pinfunction "1_1") (pintype "passive"))
    )
    (net (code "43") (name "Net-(IC11-VDD)") (class "Default")
      (node (ref "C175") (pin "1") (pinfunction "1_1") (pintype "passive"))
      (node (ref "FR41") (pin "2") (pinfunction "2_2") (pintype "passive"))
      (node (ref "IC11") (pin "4") (pinfunction "VDD_4") (pintype "power_in"))
    )
    (net (code "44") (name "Net-(IC11-VOUT)") (class "Default")
      (node (ref "IC11") (pin "6") (pinfunction "VOUT_6") (pintype "tri_state"))
      (node (ref "R72") (pin "2") (pinfunction "2_2") (pintype "passive"))
    )
    (net (code "45") (name "Net-(IC13-ADJ)") (class "Default")
      (node (ref "IC13") (pin "5") (pinfunction "ADJ_5") (pintype "input"))
      (node (ref "R74") (pin "1") (pinfunction "1_1") (pintype "passive"))
      (node (ref "R80") (pin "1") (pinfunction "1_1") (pintype "passive"))
    )
    (net (code "46") (name "Net-(IC14-FB)") (class "Default")
      (node (ref "C182") (pin "2") (pinfunction "2_2") (pintype "passive"))
      (node (ref "IC14") (pin "4") (pinfunction "FB_4") (pintype "input"))
      (node (ref "R79") (pin "1") (pinfunction "1_1") (pintype "passive"))
      (node (ref "R82") (pin "2") (pinfunction "2_2") (pintype "passive"))
    )
    (net (code "47") (name "Net-(IC16-Vdd)") (class "Default")
      (node (ref "C180") (pin "1") (pinfunction "1_1") (pintype "passive"))
      (node (ref "FR42") (pin "2") (pinfunction "2_2") (pintype "passive"))
      (node (ref "IC16") (pin "1") (pinfunction "Vdd_1") (pintype "power_in"))
      (node (ref "R76") (pin "2") (pinfunction "2_2") (pintype "passive"))
    )
    (net (code "48") (name "Net-(IC17-IN)") (class "Default")
      (node (ref "C185") (pin "1") (pinfunction "1_1") (pintype "passive"))
      (node (ref "C187") (pin "2") (pinfunction "2_2") (pintype "passive"))
      (node (ref "FR43") (pin "2") (pinfunction "2_2") (pintype "passive"))
      (node (ref "IC17") (pin "1") (pinfunction "IN_1") (pintype "power_in"))
    )
    (net (code "49") (name "Net-(IC18-ADJ)") (class "Default")
      (node (ref "IC18") (pin "5") (pinfunction "ADJ_5") (pintype "input"))
      (node (ref "R84") (pin "1") (pinfunction "1_1") (pintype "passive"))
      (node (ref "R89") (pin "1") (pinfunction "1_1") (pintype "passive"))
    )
    (net (code "50") (name "Net-(IC18-PG)") (class "Default")
      (node (ref "C192") (pin "2") (pinfunction "2_2") (pintype "passive"))
      (node (ref "IC18") (pin "3") (pinfunction "PG_3") (pintype "output"))
    )
    (net (code "51") (name "Net-(IC19-FB)") (class "Default")
      (node (ref "C193") (pin "2") (pinfunction "2_2") (pintype "passive"))
      (node (ref "IC19") (pin "4") (pinfunction "FB_4") (pintype "input"))
      (node (ref "R88") (pin "1") (pinfunction "1_1") (pintype "passive"))
      (node (ref "R91") (pin "2") (pinfunction "2_2") (pintype "passive"))
    )
    (net (code "52") (name "Net-(J9-Pad1)") (class "Default")
      (node (ref "J9") (pin "1") (pinfunction "1_1") (pintype "passive"))
      (node (ref "R100") (pin "2") (pinfunction "2_2") (pintype "passive"))
      (node (ref "VT4") (pin "D") (pinfunction "D_D") (pintype "passive"))
    )
    (net (code "53") (name "Net-(LED1-Pad3)") (class "Default")
      (node (ref "LED1") (pin "3") (pinfunction "3_3") (pintype "power_in"))
      (node (ref "R85") (pin "1") (pinfunction "1_1") (pintype "passive"))
    )
    (net (code "54") (name "Net-(LED1-Pad4)") (class "Default")
      (node (ref "LED1") (pin "4") (pinfunction "4_4") (pintype "power_in"))
      (node (ref "R87") (pin "1") (pinfunction "1_1") (pintype "passive"))
    )
    (net (code "55") (name "Net-(LED2-Pad3)") (class "Default")
      (node (ref "LED2") (pin "3") (pinfunction "3_3") (pintype "power_in"))
      (node (ref "R92") (pin "1") (pinfunction "1_1") (pintype "passive"))
    )
    (net (code "56") (name "Net-(LED2-Pad4)") (class "Default")
      (node (ref "LED2") (pin "4") (pinfunction "4_4") (pintype "power_in"))
      (node (ref "R95") (pin "1") (pinfunction "1_1") (pintype "passive"))
    )
    (net (code "57") (name "Net-(LED3-Pad3)") (class "Default")
      (node (ref "LED3") (pin "3") (pinfunction "3_3") (pintype "power_in"))
      (node (ref "R97") (pin "1") (pinfunction "1_1") (pintype "passive"))
    )
    (net (code "58") (name "Net-(LED3-Pad4)") (class "Default")
      (node (ref "LED3") (pin "4") (pinfunction "4_4") (pintype "power_in"))
      (node (ref "R99") (pin "1") (pinfunction "1_1") (pintype "passive"))
    )
    (net (code "59") (name "Net-(XO1-RF_OUT)") (class "Default")
      (node (ref "R63") (pin "1") (pinfunction "1_1") (pintype "passive"))
      (node (ref "XO1") (pin "6") (pinfunction "RF_OUT_6") (pintype "output"))
    )
    (net (code "60") (name "Net-(XO1-VC_FILTER)") (class "Default")
      (node (ref "C157") (pin "2") (pinfunction "2_2") (pintype "passive"))
      (node (ref "XO1") (pin "7") (pinfunction "VC_FILTER_7") (pintype "input"))
    )
    (net (code "61") (name "VCC1P1") (class "Default")
      (node (ref "C179") (pin "2") (pinfunction "2_2") (pintype "passive"))
      (node (ref "IC13") (pin "4") (pinfunction "Vout_4") (pintype "output"))
      (node (ref "R74") (pin "2") (pinfunction "2_2") (pintype "passive"))
    )
    (net (code "62") (name "VCC1P8") (class "Default")
      (node (ref "C177") (pin "2") (pinfunction "2_2") (pintype "passive"))
      (node (ref "C178") (pin "2") (pinfunction "2_2") (pintype "passive"))
      (node (ref "C182") (pin "1") (pinfunction "1_1") (pintype "passive"))
      (node (ref "FR40") (pin "1") (pinfunction "1_1") (pintype "passive"))
      (node (ref "IC13") (pin "1") (pinfunction "EN_1") (pintype "input"))
      (node (ref "IC13") (pin "6") (pinfunction "Vin_6") (pintype "input"))
      (node (ref "IC14") (pin "5") (pinfunction "VOUT_5") (pintype "output"))
      (node (ref "R62") (pin "2") (pinfunction "2_2") (pintype "passive"))
      (node (ref "R79") (pin "2") (pinfunction "2_2") (pintype "passive"))
      (node (ref "R93") (pin "2") (pinfunction "2_2") (pintype "passive"))
    )
    (net (code "63") (name "VCC2P5") (class "Default")
      (node (ref "C191") (pin "2") (pinfunction "2_2") (pintype "passive"))
      (node (ref "IC18") (pin "4") (pinfunction "Vout_4") (pintype "output"))
      (node (ref "R81") (pin "2") (pinfunction "2_2") (pintype "passive"))
      (node (ref "R84") (pin "2") (pinfunction "2_2") (pintype "passive"))
      (node (ref "R98") (pin "1") (pinfunction "1_1") (pintype "passive"))
    )
    (net (code "64") (name "VCC2P5_VREF") (class "Default")
      (node (ref "C186") (pin "2") (pinfunction "2_2") (pintype "passive"))
      (node (ref "IC17") (pin "2") (pinfunction "OUT_2") (pintype "power_in"))
      (node (ref "R78") (pin "1") (pinfunction "1_1") (pintype "passive"))
    )
    (net (code "65") (name "VCC3P3") (class "Default")
      (node (ref "C156") (pin "1") (pinfunction "1_1") (pintype "passive"))
      (node (ref "C174") (pin "1") (pinfunction "1_1") (pintype "passive"))
      (node (ref "C181") (pin "1") (pinfunction "1_1") (pintype "passive"))
      (node (ref "C189") (pin "2") (pinfunction "2_2") (pintype "passive"))
      (node (ref "C190") (pin "2") (pinfunction "2_2") (pintype "passive"))
      (node (ref "C193") (pin "1") (pinfunction "1_1") (pintype "passive"))
      (node (ref "FR44") (pin "1") (pinfunction "1_1") (pintype "passive"))
      (node (ref "IC10") (pin "8") (pinfunction "VCC_8") (pintype "passive"))
      (node (ref "IC12") (pin "8") (pinfunction "VCC_8") (pintype "power_in"))
      (node (ref "IC15") (pin "7") (pinfunction "HOLD_7") (pintype "passive"))
      (node (ref "IC15") (pin "8") (pinfunction "VCC_8") (pintype "passive"))
      (node (ref "IC18") (pin "1") (pinfunction "EN_1") (pintype "input"))
      (node (ref "IC18") (pin "6") (pinfunction "Vin_6") (pintype "input"))
      (node (ref "IC19") (pin "5") (pinfunction "VOUT_5") (pintype "output"))
      (node (ref "LED1") (pin "1") (pinfunction "1_1") (pintype "power_in"))
      (node (ref "LED1") (pin "2") (pinfunction "2_2") (pintype "power_in"))
      (node (ref "LED2") (pin "1") (pinfunction "1_1") (pintype "power_in"))
      (node (ref "LED2") (pin "2") (pinfunction "2_2") (pintype "power_in"))
      (node (ref "LED3") (pin "1") (pinfunction "1_1") (pintype "power_in"))
      (node (ref "LED3") (pin "2") (pinfunction "2_2") (pintype "power_in"))
      (node (ref "R101") (pin "1") (pinfunction "1_1") (pintype "passive"))
      (node (ref "R68") (pin "1") (pinfunction "1_1") (pintype "passive"))
      (node (ref "R70") (pin "1") (pinfunction "1_1") (pintype "passive"))
      (node (ref "R75") (pin "2") (pinfunction "2_2") (pintype "passive"))
      (node (ref "R77") (pin "2") (pinfunction "2_2") (pintype "passive"))
      (node (ref "R88") (pin "2") (pinfunction "2_2") (pintype "passive"))
      (node (ref "R96") (pin "1") (pinfunction "1_1") (pintype "passive"))
    )
    (net (code "66") (name "VCC3P3_CLK") (class "Default")
      (node (ref "C196") (pin "2") (pinfunction "2_2") (pintype "passive"))
      (node (ref "FR39") (pin "1") (pinfunction "1_1") (pintype "passive"))
      (node (ref "FR41") (pin "1") (pinfunction "1_1") (pintype "passive"))
      (node (ref "FR42") (pin "1") (pinfunction "1_1") (pintype "passive"))
      (node (ref "FR43") (pin "1") (pinfunction "1_1") (pintype "passive"))
      (node (ref "FR44") (pin "2") (pinfunction "2_2") (pintype "passive"))
      (node (ref "R64") (pin "2") (pinfunction "2_2") (pintype "passive"))
    )
    (net (code "67") (name "VCC3P3_XO") (class "Default")
      (node (ref "C161") (pin "2") (pinfunction "2_2") (pintype "passive"))
      (node (ref "FR38") (pin "2") (pinfunction "2_2") (pintype "passive"))
      (node (ref "R71") (pin "2") (pinfunction "2_2") (pintype "passive"))
      (node (ref "XO1") (pin "9") (pinfunction "VCC_9") (pintype "power_in"))
    )
    (net (code "68") (name "VCC5P0") (class "Default")
      (node (ref "C176") (pin "2") (pinfunction "2_2") (pintype "passive"))
      (node (ref "C188") (pin "2") (pinfunction "2_2") (pintype "passive"))
      (node (ref "IC14") (pin "2") (pinfunction "EN_2") (pintype "input"))
      (node (ref "IC14") (pin "8") (pinfunction "VIN_8") (pintype "power_in"))
      (node (ref "IC19") (pin "8") (pinfunction "VIN_8") (pintype "power_in"))
      (node (ref "R86") (pin "2") (pinfunction "2_2") (pintype "passive"))
      (node (ref "R94") (pin "1") (pinfunction "1_1") (pintype "passive"))
    )
    (net (code "69") (name "VDIO_LMS") (class "Default")
      (node (ref "C198") (pin "2") (pinfunction "2_2") (pintype "passive"))
      (node (ref "FR45") (pin "2") (pinfunction "2_2") (pintype "passive"))
    )
    (net (code "70") (name "VDIO_LMS_FPGA") (class "Default")
      (node (ref "C197") (pin "2") (pinfunction "2_2") (pintype "passive"))
      (node (ref "FR45") (pin "1") (pinfunction "1_1") (pintype "passive"))
      (node (ref "R101") (pin "2") (pinfunction "2_2") (pintype "passive"))
      (node (ref "R98") (pin "2") (pinfunction "2_2") (pintype "passive"))
    )
    (net (code "71") (name "unconnected-(IC9-CLKout3-Pad15)") (class "Default")
      (node (ref "IC9") (pin "15") (pinfunction "CLKout3_15") (pintype "passive+no_connect"))
    )
    (net (code "72") (name "unconnected-(IC9-OSCin-Pad9)") (class "Default")
      (node (ref "IC9") (pin "9") (pinfunction "OSCin_9") (pintype "passive+no_connect"))
    )
    (net (code "73") (name "unconnected-(IC9-OSCout-Pad10)") (class "Default")
      (node (ref "IC9") (pin "10") (pinfunction "OSCout_10") (pintype "passive+no_connect"))
    )
    (net (code "74") (name "unconnected-(IC14-NC-Pad7)") (class "Default")
      (node (ref "IC14") (pin "7") (pinfunction "NC_7") (pintype "passive+no_connect"))
    )
    (net (code "75") (name "unconnected-(IC14-PG-Pad1)") (class "Default")
      (node (ref "IC14") (pin "1") (pinfunction "PG_1") (pintype "output+no_connect"))
    )
    (net (code "76") (name "unconnected-(IC19-NC-Pad7)") (class "Default")
      (node (ref "IC19") (pin "7") (pinfunction "NC_7") (pintype "passive+no_connect"))
    )
    (net (code "77") (name "unconnected-(IC19-PG-Pad1)") (class "Default")
      (node (ref "IC19") (pin "1") (pinfunction "PG_1") (pintype "output+no_connect"))
    )
    (net (code "78") (name "unconnected-(XO1-NC-Pad2)") (class "Default")
      (node (ref "XO1") (pin "2") (pinfunction "NC_2") (pintype "passive+no_connect"))
    )
    (net (code "79") (name "unconnected-(XO1-NC-Pad3)") (class "Default")
      (node (ref "XO1") (pin "3") (pinfunction "NC_3") (pintype "passive+no_connect"))
    )
    (net (code "80") (name "unconnected-(XO1-NC-Pad5)") (class "Default")
      (node (ref "XO1") (pin "5") (pinfunction "NC_5") (pintype "passive+no_connect"))
    )
    (net (code "81") (name "unconnected-(XO1-NC-Pad8)") (class "Default")
      (node (ref "XO1") (pin "8") (pinfunction "NC_8") (pintype "passive+no_connect"))
    )
    (net (code "82") (name "unconnected-(XO1-NC-Pad10)") (class "Default")
      (node (ref "XO1") (pin "10") (pinfunction "NC_10") (pintype "passive+no_connect"))
    )
  )
)
